# flying-horse-foot-v3_1.net
KiCad netlist of a schematic drawn in EAGLE
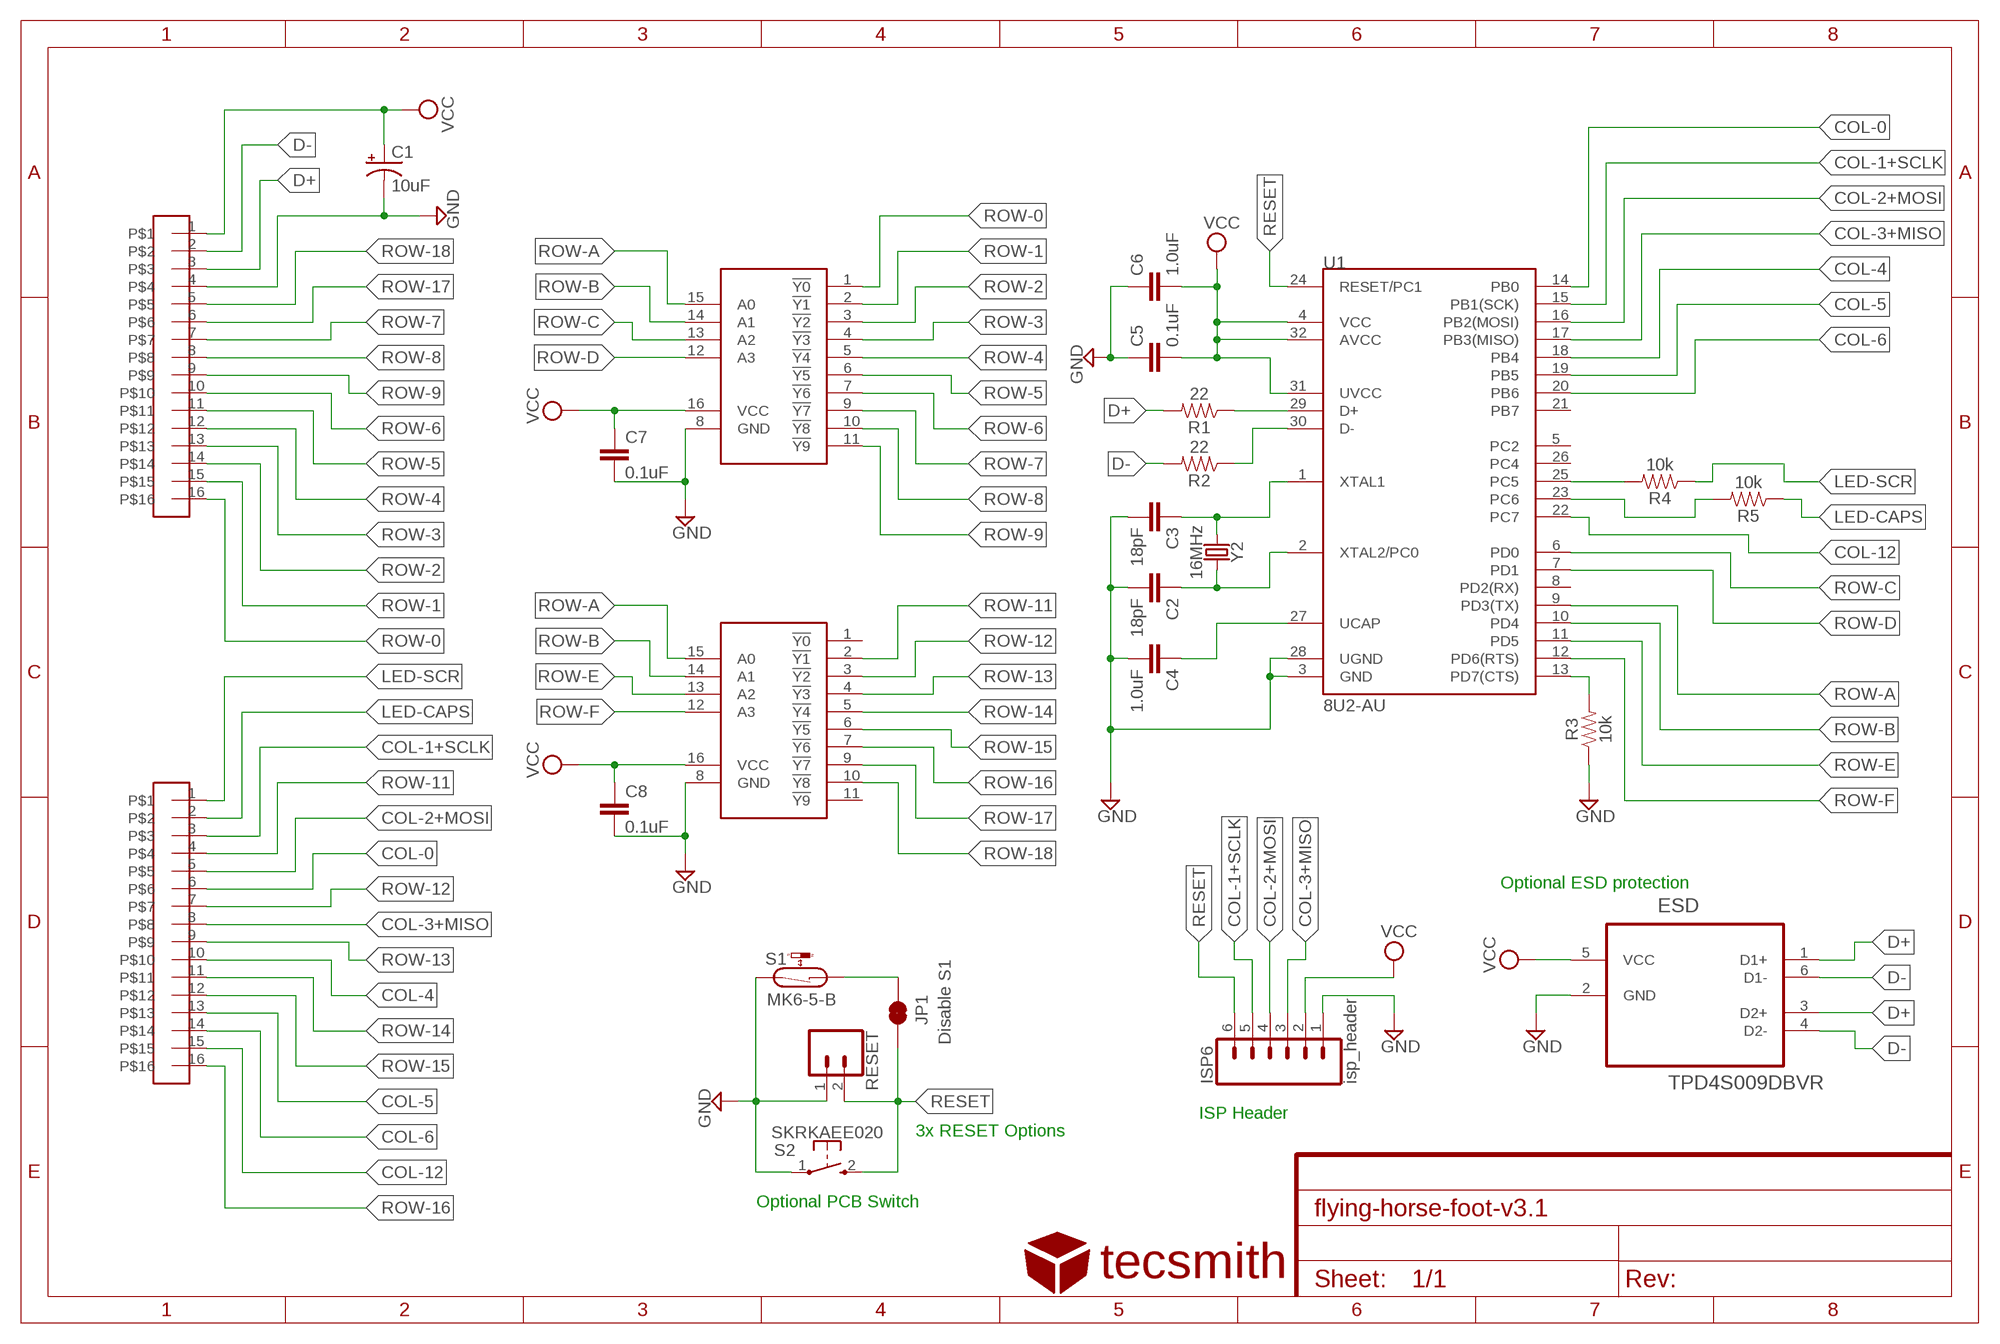
[diagram p0: schematic, sheet 1]

(export (version "E")
  (design (tool "Eeschema 10.0.6"))
  (components
    (comp (ref "C1")
      (value "10uF")
      (footprint "eagle-import:EEE-1CA100SR")
      (libsource (lib "eagle-import") (part "EEE-1CA100SR-EIA3528-20V-10%(TANT)"))
    )
    (comp (ref "C2")
      (value "18pF")
      (footprint "eagle-import:0603")
      (libsource (lib "eagle-import") (part "18PF-0603-50V-5%"))
    )
    (comp (ref "C3")
      (value "18pF")
      (footprint "eagle-import:0603")
      (libsource (lib "eagle-import") (part "18PF-0603-50V-5%"))
    )
    (comp (ref "C4")
      (value "1.0uF")
      (footprint "eagle-import:0603")
      (libsource (lib "eagle-import") (part "1.0UF-0603-16V-10%"))
    )
    (comp (ref "C5")
      (value "0.1uF")
      (footprint "eagle-import:0603")
      (libsource (lib "eagle-import") (part "0.1UF-0603-25V-5%"))
    )
    (comp (ref "C6")
      (value "1.0uF")
      (footprint "eagle-import:0603")
      (libsource (lib "eagle-import") (part "1.0UF-0603-16V-10%"))
    )
    (comp (ref "C7")
      (value "0.1uF")
      (footprint "eagle-import:0603")
      (libsource (lib "eagle-import") (part "0.1UF-0603-25V-5%"))
    )
    (comp (ref "C8")
      (value "0.1uF")
      (footprint "eagle-import:0603")
      (libsource (lib "eagle-import") (part "0.1UF-0603-25V-5%"))
    )
    (comp (ref "ESD")
      (value "TPD4S009DBVR")
      (footprint "eagle-import:SOT95P280X145-6N")
      (libsource (lib "eagle-import") (part "TPD4S009DBVR"))
    )
    (comp (ref "ISP6")
      (value "isp_header")
      (footprint "eagle-import:1X06_NO_SILK")
      (libsource (lib "eagle-import") (part "CONN_06NO_SILK_NO_POP"))
    )
    (comp (ref "JP1")
      (value "Disable S1")
      (footprint "eagle-import:SMT-JUMPER_2_NC_TRACE_NO-SILK")
      (libsource (lib "eagle-import") (part "JUMPER-SMT_2_NC_TRACE_NO-SILK"))
    )
    (comp (ref "R1")
      (value "22")
      (footprint "eagle-import:0603")
      (libsource (lib "eagle-import") (part "22OHM-0603-1/10W-1%"))
    )
    (comp (ref "R2")
      (value "22")
      (footprint "eagle-import:0603")
      (libsource (lib "eagle-import") (part "22OHM-0603-1/10W-1%"))
    )
    (comp (ref "R3")
      (value "10k")
      (footprint "eagle-import:0603")
      (libsource (lib "eagle-import") (part "10KOHM-0603-1/10W-1%"))
    )
    (comp (ref "R4")
      (value "10k")
      (footprint "eagle-import:0603")
      (libsource (lib "eagle-import") (part "10KOHM-0603-1/10W-1%"))
    )
    (comp (ref "R5")
      (value "10k")
      (footprint "eagle-import:0603")
      (libsource (lib "eagle-import") (part "10KOHM-0603-1/10W-1%"))
    )
    (comp (ref "RESET")
      (value "0.1 inch 2-pin")
      (footprint "eagle-import:1X02")
      (libsource (lib "eagle-import") (part "CONN_02"))
    )
    (comp (ref "S1")
      (value "MK6-5-B")
      (footprint "eagle-import:MK6-5")
      (fields (field (name "MF") "MEDER"))
      (libsource (lib "eagle-import") (part "REED-SWITCH-MK6-5-B"))
    )
    (comp (ref "S2")
      (value "SKRKAEE020")
      (footprint "eagle-import:SKRKAEE020")
      (libsource (lib "eagle-import") (part "MOMENTARY-SWITCH-SPST-1"))
    )
    (comp (ref "U$1")
      (value "SN74HC42DR")
      (footprint "eagle-import:D16")
      (libsource (lib "eagle-import") (part "74HC42D16"))
    )
    (comp (ref "U$2")
      (value "74HC42D16")
      (footprint "eagle-import:D16")
      (libsource (lib "eagle-import") (part "74HC42D16"))
    )
    (comp (ref "U$3")
      (value "16PIN-2MM-HEADER")
      (footprint "eagle-import:16PIN-2MM-HEADER")
      (libsource (lib "eagle-import") (part "16PIN-2MM-HEADER"))
    )
    (comp (ref "U$4")
      (value "16PIN-2MM-HEADER")
      (footprint "eagle-import:16PIN-2MM-HEADER")
      (libsource (lib "eagle-import") (part "16PIN-2MM-HEADER"))
    )
    (comp (ref "U$5")
      (value "TECSMITH-LOGO")
      (footprint "eagle-import:TECSMITH-LOGO")
      (libsource (lib "eagle-import") (part "TECSMITH-LOGO"))
    )
    (comp (ref "U1")
      (value "8U2-AU")
      (footprint "eagle-import:TQFP32-08_MCU")
      (libsource (lib "eagle-import") (part "ATMEGA8U2AU"))
    )
    (comp (ref "Y2")
      (value "16MHz")
      (footprint "eagle-import:CRYSTAL-SMD-5X3.2-4PAD")
      (libsource (lib "eagle-import") (part "CRYSTAL-16MHZSMD-5X3.2"))
    )
  )
  (nets
    (net (code "1") (name "COL-0") (class "Default")
      (node (ref "U$4") (pin "6") (pinfunction "P$6_6") (pintype "bidirectional"))
      (node (ref "U1") (pin "14") (pinfunction "PB0_14") (pintype "bidirectional"))
    )
    (net (code "2") (name "COL-1+SCLK") (class "Default")
      (node (ref "ISP6") (pin "5") (pinfunction "5_5") (pintype "passive"))
      (node (ref "U$4") (pin "3") (pinfunction "P$3_3") (pintype "bidirectional"))
      (node (ref "U1") (pin "15") (pinfunction "PB1(SCK)_15") (pintype "bidirectional"))
    )
    (net (code "3") (name "COL-2+MOSI") (class "Default")
      (node (ref "ISP6") (pin "4") (pinfunction "4_4") (pintype "passive"))
      (node (ref "U$4") (pin "5") (pinfunction "P$5_5") (pintype "bidirectional"))
      (node (ref "U1") (pin "16") (pinfunction "PB2(MOSI)_16") (pintype "bidirectional"))
    )
    (net (code "4") (name "COL-3+MISO") (class "Default")
      (node (ref "ISP6") (pin "3") (pinfunction "3_3") (pintype "passive"))
      (node (ref "U$4") (pin "8") (pinfunction "P$8_8") (pintype "bidirectional"))
      (node (ref "U1") (pin "17") (pinfunction "PB3(MISO)_17") (pintype "bidirectional"))
    )
    (net (code "5") (name "COL-4") (class "Default")
      (node (ref "U$4") (pin "10") (pinfunction "P$10_10") (pintype "bidirectional"))
      (node (ref "U1") (pin "18") (pinfunction "PB4_18") (pintype "bidirectional"))
    )
    (net (code "6") (name "COL-5") (class "Default")
      (node (ref "U$4") (pin "13") (pinfunction "P$13_13") (pintype "bidirectional"))
      (node (ref "U1") (pin "19") (pinfunction "PB5_19") (pintype "bidirectional"))
    )
    (net (code "7") (name "COL-6") (class "Default")
      (node (ref "U$4") (pin "14") (pinfunction "P$14_14") (pintype "bidirectional"))
      (node (ref "U1") (pin "20") (pinfunction "PB6_20") (pintype "bidirectional"))
    )
    (net (code "8") (name "COL-12") (class "Default")
      (node (ref "U$4") (pin "15") (pinfunction "P$15_15") (pintype "bidirectional"))
      (node (ref "U1") (pin "22") (pinfunction "PC7_22") (pintype "bidirectional"))
    )
    (net (code "9") (name "D+") (class "Default")
      (node (ref "ESD") (pin "1") (pinfunction "D1+_1") (pintype "input"))
      (node (ref "ESD") (pin "3") (pinfunction "D2+_3") (pintype "input"))
      (node (ref "R1") (pin "2") (pinfunction "2_2") (pintype "passive"))
      (node (ref "U$3") (pin "3") (pinfunction "P$3_3") (pintype "bidirectional"))
    )
    (net (code "10") (name "D-") (class "Default")
      (node (ref "ESD") (pin "4") (pinfunction "D2-_4") (pintype "input"))
      (node (ref "ESD") (pin "6") (pinfunction "D1-_6") (pintype "input"))
      (node (ref "R2") (pin "2") (pinfunction "2_2") (pintype "passive"))
      (node (ref "U$3") (pin "2") (pinfunction "P$2_2") (pintype "bidirectional"))
    )
    (net (code "11") (name "GND") (class "Default")
      (node (ref "C1") (pin "-") (pinfunction "-_-") (pintype "passive"))
      (node (ref "C2") (pin "2") (pinfunction "2_2") (pintype "passive"))
      (node (ref "C3") (pin "2") (pinfunction "2_2") (pintype "passive"))
      (node (ref "C4") (pin "2") (pinfunction "2_2") (pintype "passive"))
      (node (ref "C5") (pin "1") (pinfunction "1_1") (pintype "passive"))
      (node (ref "C6") (pin "1") (pinfunction "1_1") (pintype "passive"))
      (node (ref "C7") (pin "2") (pinfunction "2_2") (pintype "passive"))
      (node (ref "C8") (pin "2") (pinfunction "2_2") (pintype "passive"))
      (node (ref "ESD") (pin "2") (pinfunction "GND_2") (pintype "passive"))
      (node (ref "ISP6") (pin "1") (pinfunction "1_1") (pintype "passive"))
      (node (ref "R3") (pin "1") (pinfunction "1_1") (pintype "passive"))
      (node (ref "RESET") (pin "1") (pinfunction "1_1") (pintype "passive"))
      (node (ref "S1") (pin "2") (pinfunction "2_2") (pintype "passive"))
      (node (ref "S2") (pin "1") (pinfunction "1_1") (pintype "passive"))
      (node (ref "U$1") (pin "8") (pinfunction "GND_8") (pintype "bidirectional"))
      (node (ref "U$2") (pin "8") (pinfunction "GND_8") (pintype "bidirectional"))
      (node (ref "U$3") (pin "4") (pinfunction "P$4_4") (pintype "bidirectional"))
      (node (ref "U1") (pin "28") (pinfunction "UGND_28") (pintype "bidirectional"))
      (node (ref "U1") (pin "3") (pinfunction "GND_3") (pintype "bidirectional"))
    )
    (net (code "12") (name "LED-CAPS") (class "Default")
      (node (ref "R5") (pin "1") (pinfunction "1_1") (pintype "passive"))
      (node (ref "U$4") (pin "2") (pinfunction "P$2_2") (pintype "bidirectional"))
    )
    (net (code "13") (name "LED-SCR") (class "Default")
      (node (ref "R4") (pin "1") (pinfunction "1_1") (pintype "passive"))
      (node (ref "U$4") (pin "1") (pinfunction "P$1_1") (pintype "bidirectional"))
    )
    (net (code "14") (name "Net-(JP1-Pad1)") (class "Default")
      (node (ref "JP1") (pin "1") (pinfunction "1_1") (pintype "passive"))
      (node (ref "S1") (pin "1") (pinfunction "1_1") (pintype "passive"))
    )
    (net (code "15") (name "Net-(U1-D+)") (class "Default")
      (node (ref "R1") (pin "1") (pinfunction "1_1") (pintype "passive"))
      (node (ref "U1") (pin "29") (pinfunction "D+_29") (pintype "bidirectional"))
    )
    (net (code "16") (name "Net-(U1-D-)") (class "Default")
      (node (ref "R2") (pin "1") (pinfunction "1_1") (pintype "passive"))
      (node (ref "U1") (pin "30") (pinfunction "D-_30") (pintype "bidirectional"))
    )
    (net (code "17") (name "Net-(U1-PC5)") (class "Default")
      (node (ref "R4") (pin "2") (pinfunction "2_2") (pintype "passive"))
      (node (ref "U1") (pin "25") (pinfunction "PC5_25") (pintype "bidirectional"))
    )
    (net (code "18") (name "Net-(U1-PC6)") (class "Default")
      (node (ref "R5") (pin "2") (pinfunction "2_2") (pintype "passive"))
      (node (ref "U1") (pin "23") (pinfunction "PC6_23") (pintype "bidirectional"))
    )
    (net (code "19") (name "Net-(U1-PD7(CTS))") (class "Default")
      (node (ref "R3") (pin "2") (pinfunction "2_2") (pintype "passive"))
      (node (ref "U1") (pin "13") (pinfunction "PD7(CTS)_13") (pintype "bidirectional"))
    )
    (net (code "20") (name "Net-(U1-UCAP)") (class "Default")
      (node (ref "C4") (pin "1") (pinfunction "1_1") (pintype "passive"))
      (node (ref "U1") (pin "27") (pinfunction "UCAP_27") (pintype "bidirectional"))
    )
    (net (code "21") (name "Net-(U1-XTAL1)") (class "Default")
      (node (ref "C3") (pin "1") (pinfunction "1_1") (pintype "passive"))
      (node (ref "U1") (pin "1") (pinfunction "XTAL1_1") (pintype "bidirectional"))
      (node (ref "Y2") (pin "1") (pinfunction "1_1") (pintype "passive"))
    )
    (net (code "22") (name "Net-(U1-XTAL2{slash}PC0)") (class "Default")
      (node (ref "C2") (pin "1") (pinfunction "1_1") (pintype "passive"))
      (node (ref "U1") (pin "2") (pinfunction "XTAL2/PC0_2") (pintype "bidirectional"))
      (node (ref "Y2") (pin "3") (pinfunction "2_3") (pintype "passive"))
    )
    (net (code "23") (name "RESET") (class "Default")
      (node (ref "ISP6") (pin "6") (pinfunction "6_6") (pintype "passive"))
      (node (ref "JP1") (pin "2") (pinfunction "2_2") (pintype "passive"))
      (node (ref "RESET") (pin "2") (pinfunction "2_2") (pintype "passive"))
      (node (ref "S2") (pin "2") (pinfunction "3_2") (pintype "passive"))
      (node (ref "U1") (pin "24") (pinfunction "RESET/PC1_24") (pintype "bidirectional"))
    )
    (net (code "24") (name "ROW-0") (class "Default")
      (node (ref "U$1") (pin "1") (pinfunction "~{Y0}_1") (pintype "bidirectional"))
      (node (ref "U$3") (pin "16") (pinfunction "P$16_16") (pintype "bidirectional"))
    )
    (net (code "25") (name "ROW-1") (class "Default")
      (node (ref "U$1") (pin "2") (pinfunction "~{Y1}_2") (pintype "bidirectional"))
      (node (ref "U$3") (pin "15") (pinfunction "P$15_15") (pintype "bidirectional"))
    )
    (net (code "26") (name "ROW-2") (class "Default")
      (node (ref "U$1") (pin "3") (pinfunction "~{Y2}_3") (pintype "bidirectional"))
      (node (ref "U$3") (pin "14") (pinfunction "P$14_14") (pintype "bidirectional"))
    )
    (net (code "27") (name "ROW-3") (class "Default")
      (node (ref "U$1") (pin "4") (pinfunction "~{Y3}_4") (pintype "bidirectional"))
      (node (ref "U$3") (pin "13") (pinfunction "P$13_13") (pintype "bidirectional"))
    )
    (net (code "28") (name "ROW-4") (class "Default")
      (node (ref "U$1") (pin "5") (pinfunction "~{Y4}_5") (pintype "bidirectional"))
      (node (ref "U$3") (pin "12") (pinfunction "P$12_12") (pintype "bidirectional"))
    )
    (net (code "29") (name "ROW-5") (class "Default")
      (node (ref "U$1") (pin "6") (pinfunction "~{Y5}_6") (pintype "bidirectional"))
      (node (ref "U$3") (pin "11") (pinfunction "P$11_11") (pintype "bidirectional"))
    )
    (net (code "30") (name "ROW-6") (class "Default")
      (node (ref "U$1") (pin "7") (pinfunction "~{Y6}_7") (pintype "bidirectional"))
      (node (ref "U$3") (pin "10") (pinfunction "P$10_10") (pintype "bidirectional"))
    )
    (net (code "31") (name "ROW-7") (class "Default")
      (node (ref "U$1") (pin "9") (pinfunction "~{Y7}_9") (pintype "bidirectional"))
      (node (ref "U$3") (pin "7") (pinfunction "P$7_7") (pintype "bidirectional"))
    )
    (net (code "32") (name "ROW-8") (class "Default")
      (node (ref "U$1") (pin "10") (pinfunction "~{Y8}_10") (pintype "bidirectional"))
      (node (ref "U$3") (pin "8") (pinfunction "P$8_8") (pintype "bidirectional"))
    )
    (net (code "33") (name "ROW-9") (class "Default")
      (node (ref "U$1") (pin "11") (pinfunction "~{Y9}_11") (pintype "bidirectional"))
      (node (ref "U$3") (pin "9") (pinfunction "P$9_9") (pintype "bidirectional"))
    )
    (net (code "34") (name "ROW-11") (class "Default")
      (node (ref "U$2") (pin "2") (pinfunction "~{Y1}_2") (pintype "bidirectional"))
      (node (ref "U$4") (pin "4") (pinfunction "P$4_4") (pintype "bidirectional"))
    )
    (net (code "35") (name "ROW-12") (class "Default")
      (node (ref "U$2") (pin "3") (pinfunction "~{Y2}_3") (pintype "bidirectional"))
      (node (ref "U$4") (pin "7") (pinfunction "P$7_7") (pintype "bidirectional"))
    )
    (net (code "36") (name "ROW-13") (class "Default")
      (node (ref "U$2") (pin "4") (pinfunction "~{Y3}_4") (pintype "bidirectional"))
      (node (ref "U$4") (pin "9") (pinfunction "P$9_9") (pintype "bidirectional"))
    )
    (net (code "37") (name "ROW-14") (class "Default")
      (node (ref "U$2") (pin "5") (pinfunction "~{Y4}_5") (pintype "bidirectional"))
      (node (ref "U$4") (pin "11") (pinfunction "P$11_11") (pintype "bidirectional"))
    )
    (net (code "38") (name "ROW-15") (class "Default")
      (node (ref "U$2") (pin "6") (pinfunction "~{Y5}_6") (pintype "bidirectional"))
      (node (ref "U$4") (pin "12") (pinfunction "P$12_12") (pintype "bidirectional"))
    )
    (net (code "39") (name "ROW-16") (class "Default")
      (node (ref "U$2") (pin "7") (pinfunction "~{Y6}_7") (pintype "bidirectional"))
      (node (ref "U$4") (pin "16") (pinfunction "P$16_16") (pintype "bidirectional"))
    )
    (net (code "40") (name "ROW-17") (class "Default")
      (node (ref "U$2") (pin "9") (pinfunction "~{Y7}_9") (pintype "bidirectional"))
      (node (ref "U$3") (pin "6") (pinfunction "P$6_6") (pintype "bidirectional"))
    )
    (net (code "41") (name "ROW-18") (class "Default")
      (node (ref "U$2") (pin "10") (pinfunction "~{Y8}_10") (pintype "bidirectional"))
      (node (ref "U$3") (pin "5") (pinfunction "P$5_5") (pintype "bidirectional"))
    )
    (net (code "42") (name "ROW-A") (class "Default")
      (node (ref "U$1") (pin "15") (pinfunction "A0_15") (pintype "bidirectional"))
      (node (ref "U$2") (pin "15") (pinfunction "A0_15") (pintype "bidirectional"))
      (node (ref "U1") (pin "9") (pinfunction "PD3(TX)_9") (pintype "bidirectional"))
    )
    (net (code "43") (name "ROW-B") (class "Default")
      (node (ref "U$1") (pin "14") (pinfunction "A1_14") (pintype "bidirectional"))
      (node (ref "U$2") (pin "14") (pinfunction "A1_14") (pintype "bidirectional"))
      (node (ref "U1") (pin "10") (pinfunction "PD4_10") (pintype "bidirectional"))
    )
    (net (code "44") (name "ROW-C") (class "Default")
      (node (ref "U$1") (pin "13") (pinfunction "A2_13") (pintype "bidirectional"))
      (node (ref "U1") (pin "6") (pinfunction "PD0_6") (pintype "bidirectional"))
    )
    (net (code "45") (name "ROW-D") (class "Default")
      (node (ref "U$1") (pin "12") (pinfunction "A3_12") (pintype "bidirectional"))
      (node (ref "U1") (pin "7") (pinfunction "PD1_7") (pintype "bidirectional"))
    )
    (net (code "46") (name "ROW-E") (class "Default")
      (node (ref "U$2") (pin "13") (pinfunction "A2_13") (pintype "bidirectional"))
      (node (ref "U1") (pin "11") (pinfunction "PD5_11") (pintype "bidirectional"))
    )
    (net (code "47") (name "ROW-F") (class "Default")
      (node (ref "U$2") (pin "12") (pinfunction "A3_12") (pintype "bidirectional"))
      (node (ref "U1") (pin "12") (pinfunction "PD6(RTS)_12") (pintype "bidirectional"))
    )
    (net (code "48") (name "VCC") (class "Default")
      (node (ref "C1") (pin "+") (pinfunction "+_+") (pintype "passive"))
      (node (ref "C5") (pin "2") (pinfunction "2_2") (pintype "passive"))
      (node (ref "C6") (pin "2") (pinfunction "2_2") (pintype "passive"))
      (node (ref "C7") (pin "1") (pinfunction "1_1") (pintype "passive"))
      (node (ref "C8") (pin "1") (pinfunction "1_1") (pintype "passive"))
      (node (ref "ESD") (pin "5") (pinfunction "VCC_5") (pintype "power_in"))
      (node (ref "ISP6") (pin "2") (pinfunction "2_2") (pintype "passive"))
      (node (ref "U$1") (pin "16") (pinfunction "VCC_16") (pintype "bidirectional"))
      (node (ref "U$2") (pin "16") (pinfunction "VCC_16") (pintype "bidirectional"))
      (node (ref "U$3") (pin "1") (pinfunction "P$1_1") (pintype "bidirectional"))
      (node (ref "U1") (pin "31") (pinfunction "UVCC_31") (pintype "bidirectional"))
      (node (ref "U1") (pin "32") (pinfunction "AVCC_32") (pintype "bidirectional"))
      (node (ref "U1") (pin "4") (pinfunction "VCC_4") (pintype "bidirectional"))
    )
    (net (code "49") (name "unconnected-(U$2-~{Y0}-Pad1)") (class "Default")
      (node (ref "U$2") (pin "1") (pinfunction "~{Y0}_1") (pintype "bidirectional"))
    )
    (net (code "50") (name "unconnected-(U$2-~{Y9}-Pad11)") (class "Default")
      (node (ref "U$2") (pin "11") (pinfunction "~{Y9}_11") (pintype "bidirectional"))
    )
    (net (code "51") (name "unconnected-(U1-PB7-Pad21)") (class "Default")
      (node (ref "U1") (pin "21") (pinfunction "PB7_21") (pintype "bidirectional"))
    )
    (net (code "52") (name "unconnected-(U1-PC2-Pad5)") (class "Default")
      (node (ref "U1") (pin "5") (pinfunction "PC2_5") (pintype "bidirectional"))
    )
    (net (code "53") (name "unconnected-(U1-PC4-Pad26)") (class "Default")
      (node (ref "U1") (pin "26") (pinfunction "PC4_26") (pintype "bidirectional"))
    )
    (net (code "54") (name "unconnected-(U1-PD2(RX)-Pad8)") (class "Default")
      (node (ref "U1") (pin "8") (pinfunction "PD2(RX)_8") (pintype "bidirectional"))
    )
  )
)
